# MCU.net
KiCad netlist of a schematic drawn in Altium Designer
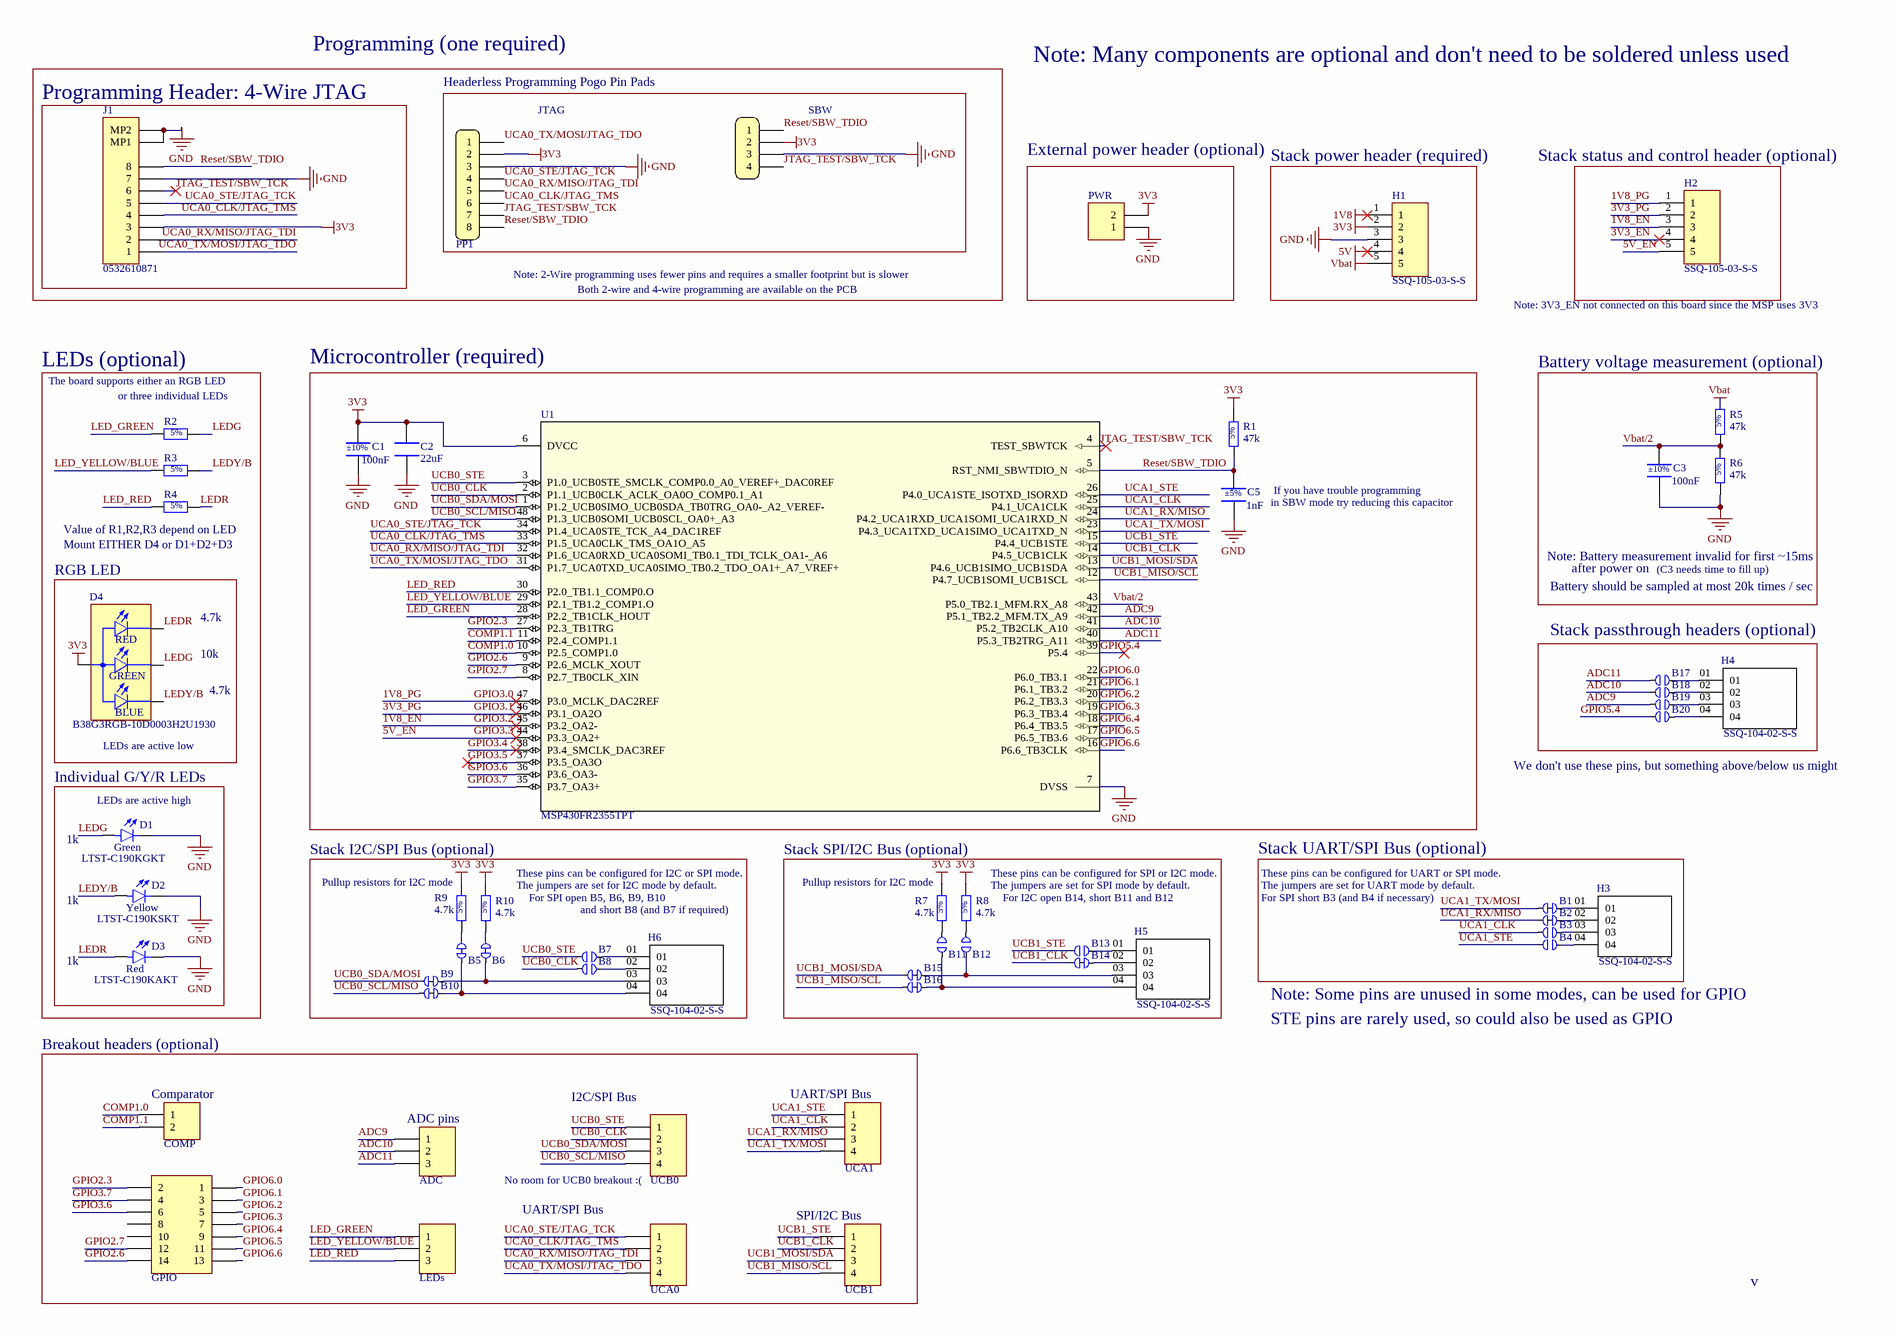
[diagram p0: MCU.SchDoc, left]
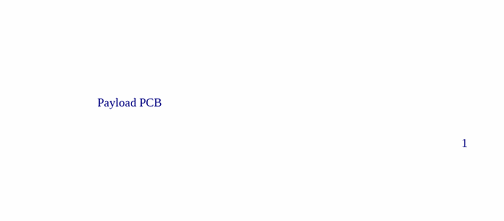
[diagram p1: MCU.SchDoc, right]

(export (version "E")
  (design (tool "Eeschema 10.0.6"))
  (components
    (comp (ref "ADC")
      (value "Header 3")
      (footprint "HDR1X3")
      (description "Header, 3-Pin")
      (libsource (lib "Miscellaneous Connectors") (part "Header 3"))
    )
    (comp (ref "B1")
      (value "Solder Jumper Normally Closed 0201")
      (footprint "Solder Bridge Closed 0201")
      (libsource (lib "APSS Generic Components") (part "Solder Jumper Normally Closed 0201"))
    )
    (comp (ref "B2")
      (value "Solder Jumper Normally Closed 0201")
      (footprint "Solder Bridge Closed 0201")
      (libsource (lib "APSS Generic Components") (part "Solder Jumper Normally Closed 0201"))
    )
    (comp (ref "B3")
      (value "Solder Jumper Normally Open 0201")
      (footprint "Solder Bridge Open 0201")
      (libsource (lib "APSS Generic Components") (part "Solder Jumper Normally Open 0201"))
    )
    (comp (ref "B4")
      (value "Solder Jumper Normally Open 0201")
      (footprint "Solder Bridge Open 0201")
      (libsource (lib "APSS Generic Components") (part "Solder Jumper Normally Open 0201"))
    )
    (comp (ref "B5")
      (value "Solder Jumper Normally Closed 0201")
      (footprint "Solder Bridge Closed 0201")
      (libsource (lib "APSS Generic Components") (part "Solder Jumper Normally Closed 0201"))
    )
    (comp (ref "B6")
      (value "Solder Jumper Normally Closed 0201")
      (footprint "Solder Bridge Closed 0201")
      (libsource (lib "APSS Generic Components") (part "Solder Jumper Normally Closed 0201"))
    )
    (comp (ref "B7")
      (value "Solder Jumper Normally Open 0201")
      (footprint "Solder Bridge Open 0201")
      (libsource (lib "") (part "Solder Jumper Normally Open 0201_1"))
    )
    (comp (ref "B8")
      (value "Solder Jumper Normally Open 0201")
      (footprint "Solder Bridge Open 0201")
      (libsource (lib "") (part "Solder Jumper Normally Open 0201_1"))
    )
    (comp (ref "B9")
      (value "Solder Jumper Normally Closed 0201")
      (footprint "Solder Bridge Closed 0201")
      (libsource (lib "APSS Generic Components") (part "Solder Jumper Normally Closed 0201"))
    )
    (comp (ref "B10")
      (value "Solder Jumper Normally Closed 0201")
      (footprint "Solder Bridge Closed 0201")
      (libsource (lib "APSS Generic Components") (part "Solder Jumper Normally Closed 0201"))
    )
    (comp (ref "B11")
      (value "Solder Jumper Normally Open 0201")
      (footprint "Solder Bridge Open 0201")
      (libsource (lib "APSS Generic Components") (part "Solder Jumper Normally Open 0201"))
    )
    (comp (ref "B12")
      (value "Solder Jumper Normally Open 0201")
      (footprint "Solder Bridge Open 0201")
      (libsource (lib "APSS Generic Components") (part "Solder Jumper Normally Open 0201"))
    )
    (comp (ref "B13")
      (value "Solder Jumper Normally Open 0201")
      (footprint "Solder Bridge Open 0201")
      (libsource (lib "APSS Generic Components") (part "Solder Jumper Normally Open 0201"))
    )
    (comp (ref "B14")
      (value "Solder Jumper Normally Closed 0201")
      (footprint "Solder Bridge Closed 0201")
      (libsource (lib "APSS Generic Components") (part "Solder Jumper Normally Closed 0201"))
    )
    (comp (ref "B15")
      (value "Solder Jumper Normally Closed 0201")
      (footprint "Solder Bridge Closed 0201")
      (libsource (lib "APSS Generic Components") (part "Solder Jumper Normally Closed 0201"))
    )
    (comp (ref "B16")
      (value "Solder Jumper Normally Closed 0201")
      (footprint "Solder Bridge Closed 0201")
      (libsource (lib "APSS Generic Components") (part "Solder Jumper Normally Closed 0201"))
    )
    (comp (ref "B17")
      (value "Solder Jumper Normally Open 0201")
      (footprint "Solder Bridge Open 0201")
      (libsource (lib "APSS Generic Components") (part "Solder Jumper Normally Open 0201"))
    )
    (comp (ref "B18")
      (value "Solder Jumper Normally Open 0201")
      (footprint "Solder Bridge Open 0201")
      (libsource (lib "APSS Generic Components") (part "Solder Jumper Normally Open 0201"))
    )
    (comp (ref "B19")
      (value "Solder Jumper Normally Open 0201")
      (footprint "Solder Bridge Open 0201")
      (libsource (lib "APSS Generic Components") (part "Solder Jumper Normally Open 0201"))
    )
    (comp (ref "B20")
      (value "Solder Jumper Normally Open 0201")
      (footprint "Solder Bridge Open 0201")
      (libsource (lib "APSS Generic Components") (part "Solder Jumper Normally Open 0201"))
    )
    (comp (ref "C1")
      (value "100nF")
      (footprint "APSS Generic Components:CAPACITOR_0805_2012M-70N")
      (description "Generic Capacitor")
      (fields (field (name "TOLERANCE") "±10%") (field (name "MF PART NO.") "C0805C104K5RAC7800"))
      (libsource (lib "General Components") (part "Generic Capacitor"))
    )
    (comp (ref "C2")
      (value "22uF")
      (footprint "APSS Prototype Parts:CAPACITOR_0805_2012M-70N")
      (description "Passive - Capacitor, X5R, 22uF Max, 6.3V, 0805 (2012 Metric), ±20%, -55°C ~ 85°C. 8.8uF @ 5V")
      (fields (field (name "TOLERANCE") "±20%") (field (name "MF PART NO.") "C0805C226M9PACTU"))
      (libsource (lib "APSS Prototype Parts") (part "C0805C226M9PACTU"))
    )
    (comp (ref "C3")
      (value "100nF")
      (footprint "APSS Generic Components:CAPACITOR_0805_2012M-70N")
      (description "Generic Capacitor")
      (fields (field (name "TOLERANCE") "±10%") (field (name "MF PART NO.") "C0805C104K5RAC7800"))
      (libsource (lib "APSS Generic Components") (part "Generic Capacitor"))
    )
    (comp (ref "C5")
      (value "1nF")
      (footprint "APSS Generic Components:CAPACITOR_0805_2012M-70N")
      (description "Generic Capacitor")
      (fields (field (name "TOLERANCE") "±5%") (field (name "MF PART NO.") "399-C0805C102J5GAC7800CT-ND"))
      (libsource (lib "APSS Generic Components") (part "Generic Capacitor"))
    )
    (comp (ref "COMP")
      (value "Header 2")
      (footprint "HDR1X2")
      (description "Header, 2-Pin")
      (libsource (lib "Miscellaneous Connectors") (part "Header 2"))
    )
    (comp (ref "D1")
      (value "LTST-C190 Series")
      (footprint "APSS Prototype Parts:LED_0603_1608M_0.80mm")
      (description "Diode - LED, 0603")
      (fields
        (field (name "MF PART NO.") "LTST-C190KGKT")
        (field (name "COLOUR") "Green")
        (field (name "APSS STANDARD PART") "APSS Standard")
      )
      (libsource (lib "APSS Prototype Parts") (part "LTST-C190 Series"))
    )
    (comp (ref "D2")
      (value "LTST-C190 Series")
      (footprint "APSS Prototype Parts:LED_0603_1608M_0.80mm")
      (description "Diode - LED, 0603")
      (fields
        (field (name "MF PART NO.") "LTST-C190KSKT")
        (field (name "COLOUR") "Yellow")
        (field (name "APSS STANDARD PART") "APSS Standard")
      )
      (libsource (lib "APSS Prototype Parts") (part "LTST-C190 Series"))
    )
    (comp (ref "D3")
      (value "LTST-C190 Series")
      (footprint "APSS Prototype Parts:LED_0603_1608M_0.80mm")
      (description "Diode - LED, 0603")
      (fields
        (field (name "MF PART NO.") "LTST-C190KAKT")
        (field (name "COLOUR") "Red")
        (field (name "APSS STANDARD PART") "APSS Standard")
      )
      (libsource (lib "APSS Prototype Parts") (part "LTST-C190 Series"))
    )
    (comp (ref "D4")
      (value "B38G3RGB-10D0003H2U1930")
      (footprint "APSS Prototype Parts:LED_B38G3RGB-10D0003H2U1930_0606_1616M")
      (description "Diode - LED, RGB, 2V Red, 3V Green, 3V Blue 0606 (1616 Metric)")
      (fields (field (name "APSS STANDARD PART") "APSS Standard"))
      (libsource (lib "APSS Prototype Parts") (part "B38G3RGB-10D0003H2U1930"))
    )
    (comp (ref "GPIO")
      (value "Header 7X2")
      (footprint "HDR2X7")
      (description "Header, 7-Pin, Dual row")
      (libsource (lib "Miscellaneous Connectors") (part "Header 7X2"))
    )
    (comp (ref "H1")
      (value "SSQ-105-03-S-S")
      (footprint "SAMTEC_SSQ-105-03-S-S:SAMTEC_SSQ-105-03-S-S")
      (libsource (lib "SSQ-105-03-S-S") (part "SSQ-105-03-S-S"))
    )
    (comp (ref "H2")
      (value "SSQ-105-03-S-S")
      (footprint "SAMTEC_SSQ-105-03-S-S:SAMTEC_SSQ-105-03-S-S")
      (libsource (lib "SSQ-105-03-S-S") (part "SSQ-105-03-S-S"))
    )
    (comp (ref "H3")
      (value "SSQ-104-02-S-S")
      (footprint "*SAMTEC_SSQ-104-02-S-S_SSQ-104-02-S-S(Primary)")
      (libsource (lib "SSQ-104-02-S-S") (part "SSQ-104-02-S-S"))
    )
    (comp (ref "H4")
      (value "SSQ-104-02-S-S")
      (footprint "*SAMTEC_SSQ-104-02-S-S_SSQ-104-02-S-S(Primary)")
      (libsource (lib "SSQ-104-02-S-S") (part "SSQ-104-02-S-S"))
    )
    (comp (ref "H5")
      (value "SSQ-104-02-S-S")
      (footprint "*SAMTEC_SSQ-104-02-S-S_SSQ-104-02-S-S(Primary)")
      (libsource (lib "SSQ-104-02-S-S") (part "SSQ-104-02-S-S"))
    )
    (comp (ref "H6")
      (value "SSQ-104-02-S-S")
      (footprint "*SAMTEC_SSQ-104-02-S-S_SSQ-104-02-S-S(Primary)")
      (libsource (lib "SSQ-104-02-S-S") (part "SSQ-104-02-S-S"))
    )
    (comp (ref "J1")
      (value "0532610871")
      (footprint "APSS Prototype Parts:MOLEX_0532610871")
      (description "Header - Picoblade 08-pin, SMT, RA")
      (fields (field (name "MF PART NO.") "0532610871") (field (name "APSS STANDARD PART") "APSS Standard"))
      (libsource (lib "APSS Prototype Parts") (part "0532610871"))
    )
    (comp (ref "LEDs")
      (value "Header 3")
      (footprint "HDR1X3")
      (description "Header, 3-Pin")
      (libsource (lib "Miscellaneous Connectors") (part "Header 3"))
    )
    (comp (ref "PP1")
      (value "Headerless Pogo Holes 8-pin")
      (footprint "POGO_8_PIN_HEADER")
      (libsource (lib "APSS Generic Components") (part "Headerless Pogo Holes 8-pin"))
    )
    (comp (ref "PP2")
      (value "Headerless Pogo Holes 4-pin")
      (footprint "APSS Generic Components:POGO_4_PIN_HEADER")
      (libsource (lib "APSS Generic Components") (part "Headerless Pogo Holes 4-pin"))
    )
    (comp (ref "PWR")
      (value "~")
      (footprint "HDR1X2")
      (description "Header, 2-Pin")
      (libsource (lib "") (part "Header 2_1"))
    )
    (comp (ref "R1")
      (value "47k")
      (footprint "APSS Flight Parts:Resistor_0805_2012M-50N")
      (fields
        (field (name "TOLERANCE") "5%")
        (field (name "POWER") "1/8W")
        (field (name "MF PART NO.") "RMCF0805JT47K0")
      )
      (libsource (lib "") (part "RMCF0805JT Series_1"))
    )
    (comp (ref "R2")
      (value "1k")
      (footprint "APSS Flight Parts:Resistor_0805_2012M-50N")
      (fields
        (field (name "TOLERANCE") "5%")
        (field (name "POWER") "1/8W")
        (field (name "MF PART NO.") "RMCF0805JT1K00")
      )
      (libsource (lib "APSS Prototype Parts") (part "RMCF0805JT Series"))
    )
    (comp (ref "R3")
      (value "1k")
      (footprint "APSS Flight Parts:Resistor_0805_2012M-50N")
      (fields
        (field (name "TOLERANCE") "5%")
        (field (name "POWER") "1/8W")
        (field (name "MF PART NO.") "RMCF0805JT1K00")
      )
      (libsource (lib "APSS Prototype Parts") (part "RMCF0805JT Series"))
    )
    (comp (ref "R4")
      (value "1k")
      (footprint "APSS Flight Parts:Resistor_0805_2012M-50N")
      (fields
        (field (name "TOLERANCE") "5%")
        (field (name "POWER") "1/8W")
        (field (name "MF PART NO.") "RMCF0805JT1K00")
      )
      (libsource (lib "APSS Prototype Parts") (part "RMCF0805JT Series"))
    )
    (comp (ref "R5")
      (value "47k")
      (footprint "APSS Flight Parts:Resistor_0805_2012M-50N")
      (fields
        (field (name "TOLERANCE") "5%")
        (field (name "POWER") "1/8W")
        (field (name "MF PART NO.") "RMCF0805JT147K0")
      )
      (libsource (lib "") (part "RMCF0805JT Series_1"))
    )
    (comp (ref "R6")
      (value "47k")
      (footprint "APSS Flight Parts:Resistor_0805_2012M-50N")
      (fields
        (field (name "TOLERANCE") "5%")
        (field (name "POWER") "1/8W")
        (field (name "MF PART NO.") "RMCF0805JT47K0")
      )
      (libsource (lib "") (part "RMCF0805JT Series_1"))
    )
    (comp (ref "R7")
      (value "4.7k")
      (footprint "APSS Flight Parts:Resistor_0805_2012M-50N")
      (fields
        (field (name "TOLERANCE") "5%")
        (field (name "POWER") "1/8W")
        (field (name "MF PART NO.") "RMCF0805JT4K70")
      )
      (libsource (lib "") (part "RMCF0805JT Series_1"))
    )
    (comp (ref "R8")
      (value "4.7k")
      (footprint "APSS Flight Parts:Resistor_0805_2012M-50N")
      (fields
        (field (name "TOLERANCE") "5%")
        (field (name "POWER") "1/8W")
        (field (name "MF PART NO.") "RMCF0805JT4K70")
      )
      (libsource (lib "") (part "RMCF0805JT Series_1"))
    )
    (comp (ref "R9")
      (value "4.7k")
      (footprint "APSS Flight Parts:Resistor_0805_2012M-50N")
      (fields
        (field (name "TOLERANCE") "5%")
        (field (name "POWER") "1/8W")
        (field (name "MF PART NO.") "RMCF0805JT4K70")
      )
      (libsource (lib "") (part "RMCF0805JT Series_1"))
    )
    (comp (ref "R10")
      (value "4.7k")
      (footprint "APSS Flight Parts:Resistor_0805_2012M-50N")
      (fields
        (field (name "TOLERANCE") "5%")
        (field (name "POWER") "1/8W")
        (field (name "MF PART NO.") "RMCF0805JT4K70")
      )
      (libsource (lib "") (part "RMCF0805JT Series_1"))
    )
    (comp (ref "U1")
      (value "MSP430FR2355TPT")
      (footprint "PT0048A_L")
      (fields (field (name "APSS STANDARD PART") "APSS Standard"))
      (libsource (lib "MSP430") (part "MSP430FR2355IPT"))
    )
    (comp (ref "UCA0")
      (value "Header 4")
      (footprint "HDR1X4")
      (description "Header, 4-Pin")
      (libsource (lib "Miscellaneous Connectors") (part "Header 4"))
    )
    (comp (ref "UCA1")
      (value "Header 4")
      (footprint "HDR1X4")
      (description "Header, 4-Pin")
      (libsource (lib "Miscellaneous Connectors") (part "Header 4"))
    )
    (comp (ref "UCB0")
      (value "Header 4")
      (footprint "HDR1X4")
      (description "Header, 4-Pin")
      (libsource (lib "Miscellaneous Connectors") (part "Header 4"))
    )
    (comp (ref "UCB1")
      (value "Header 4")
      (footprint "HDR1X4")
      (description "Header, 4-Pin")
      (libsource (lib "Miscellaneous Connectors") (part "Header 4"))
    )
  )
  (nets
    (net (code "1") (name "/1V8_EN") (class "Default")
      (node (ref "H2") (pin "3") (pinfunction "3_3") (pintype "passive"))
      (node (ref "U1") (pin "45") (pinfunction "P3.2_OA2-_45") (pintype "bidirectional"))
    )
    (net (code "2") (name "/1V8_PG") (class "Default")
      (node (ref "H2") (pin "1") (pinfunction "1_1") (pintype "passive"))
      (node (ref "U1") (pin "47") (pinfunction "P3.0_MCLK_DAC2REF_47") (pintype "bidirectional"))
    )
    (net (code "3") (name "/3V3_EN") (class "Default")
      (node (ref "H2") (pin "4") (pinfunction "4_4") (pintype "passive+no_connect"))
    )
    (net (code "4") (name "/3V3_PG") (class "Default")
      (node (ref "H2") (pin "2") (pinfunction "2_2") (pintype "passive"))
      (node (ref "U1") (pin "46") (pinfunction "P3.1_OA2O_46") (pintype "bidirectional"))
    )
    (net (code "5") (name "/5V_EN") (class "Default")
      (node (ref "H2") (pin "5") (pinfunction "5_5") (pintype "passive"))
      (node (ref "U1") (pin "44") (pinfunction "P3.3_OA2+_44") (pintype "bidirectional"))
    )
    (net (code "7") (name "/ADC9") (class "Default")
      (node (ref "ADC") (pin "1") (pinfunction "1_1") (pintype "passive"))
      (node (ref "B19") (pin "1") (pinfunction "1_1") (pintype "passive"))
      (node (ref "U1") (pin "42") (pinfunction "P5.1_TB2.2_MFM.TX_A9_42") (pintype "bidirectional"))
    )
    (net (code "8") (name "/ADC10") (class "Default")
      (node (ref "ADC") (pin "2") (pinfunction "2_2") (pintype "passive"))
      (node (ref "B18") (pin "1") (pinfunction "1_1") (pintype "passive"))
      (node (ref "U1") (pin "41") (pinfunction "P5.2_TB2CLK_A10_41") (pintype "bidirectional"))
    )
    (net (code "9") (name "/ADC11") (class "Default")
      (node (ref "ADC") (pin "3") (pinfunction "3_3") (pintype "passive"))
      (node (ref "B17") (pin "1") (pinfunction "1_1") (pintype "passive"))
      (node (ref "U1") (pin "40") (pinfunction "P5.3_TB2TRG_A11_40") (pintype "bidirectional"))
    )
    (net (code "10") (name "/COMP1.0") (class "Default")
      (node (ref "COMP") (pin "1") (pinfunction "1_1") (pintype "passive"))
      (node (ref "U1") (pin "10") (pinfunction "P2.5_COMP1.0_10") (pintype "bidirectional"))
    )
    (net (code "11") (name "/COMP1.1") (class "Default")
      (node (ref "COMP") (pin "2") (pinfunction "2_2") (pintype "passive"))
      (node (ref "U1") (pin "11") (pinfunction "P2.4_COMP1.1_11") (pintype "bidirectional"))
    )
    (net (code "12") (name "/GPIO2.3") (class "Default")
      (node (ref "GPIO") (pin "2") (pinfunction "2_2") (pintype "passive"))
      (node (ref "U1") (pin "27") (pinfunction "P2.3_TB1TRG_27") (pintype "bidirectional"))
    )
    (net (code "13") (name "/GPIO2.6") (class "Default")
      (node (ref "GPIO") (pin "14") (pinfunction "14_14") (pintype "passive"))
      (node (ref "U1") (pin "9") (pinfunction "P2.6_MCLK_XOUT_9") (pintype "bidirectional"))
    )
    (net (code "14") (name "/GPIO2.7") (class "Default")
      (node (ref "GPIO") (pin "12") (pinfunction "12_12") (pintype "passive"))
      (node (ref "U1") (pin "8") (pinfunction "P2.7_TB0CLK_XIN_8") (pintype "bidirectional"))
    )
    (net (code "15") (name "/GPIO3.4") (class "Default")
      (node (ref "U1") (pin "38") (pinfunction "P3.4_SMCLK_DAC3REF_38") (pintype "bidirectional+no_connect"))
    )
    (net (code "16") (name "/GPIO3.5") (class "Default")
      (node (ref "U1") (pin "37") (pinfunction "P3.5_OA3O_37") (pintype "bidirectional+no_connect"))
    )
    (net (code "17") (name "/GPIO3.6") (class "Default")
      (node (ref "GPIO") (pin "6") (pinfunction "6_6") (pintype "passive"))
      (node (ref "U1") (pin "36") (pinfunction "P3.6_OA3-_36") (pintype "bidirectional"))
    )
    (net (code "18") (name "/GPIO3.7") (class "Default")
      (node (ref "GPIO") (pin "4") (pinfunction "4_4") (pintype "passive"))
      (node (ref "U1") (pin "35") (pinfunction "P3.7_OA3+_35") (pintype "bidirectional"))
    )
    (net (code "19") (name "/GPIO5.4") (class "Default")
      (node (ref "B20") (pin "1") (pinfunction "1_1") (pintype "passive"))
      (node (ref "U1") (pin "39") (pinfunction "P5.4_39") (pintype "bidirectional"))
    )
    (net (code "20") (name "/GPIO6.0") (class "Default")
      (node (ref "GPIO") (pin "1") (pinfunction "1_1") (pintype "passive"))
      (node (ref "U1") (pin "22") (pinfunction "P6.0_TB3.1_22") (pintype "bidirectional"))
    )
    (net (code "21") (name "/GPIO6.1") (class "Default")
      (node (ref "GPIO") (pin "3") (pinfunction "3_3") (pintype "passive"))
      (node (ref "U1") (pin "21") (pinfunction "P6.1_TB3.2_21") (pintype "bidirectional"))
    )
    (net (code "22") (name "/GPIO6.2") (class "Default")
      (node (ref "GPIO") (pin "5") (pinfunction "5_5") (pintype "passive"))
      (node (ref "U1") (pin "20") (pinfunction "P6.2_TB3.3_20") (pintype "bidirectional"))
    )
    (net (code "23") (name "/GPIO6.3") (class "Default")
      (node (ref "GPIO") (pin "7") (pinfunction "7_7") (pintype "passive"))
      (node (ref "U1") (pin "19") (pinfunction "P6.3_TB3.4_19") (pintype "bidirectional"))
    )
    (net (code "24") (name "/GPIO6.4") (class "Default")
      (node (ref "GPIO") (pin "9") (pinfunction "9_9") (pintype "passive"))
      (node (ref "U1") (pin "18") (pinfunction "P6.4_TB3.5_18") (pintype "bidirectional"))
    )
    (net (code "25") (name "/GPIO6.5") (class "Default")
      (node (ref "GPIO") (pin "11") (pinfunction "11_11") (pintype "passive"))
      (node (ref "U1") (pin "17") (pinfunction "P6.5_TB3.6_17") (pintype "bidirectional"))
    )
    (net (code "26") (name "/GPIO6.6") (class "Default")
      (node (ref "GPIO") (pin "13") (pinfunction "13_13") (pintype "passive"))
      (node (ref "U1") (pin "16") (pinfunction "P6.6_TB3CLK_16") (pintype "bidirectional"))
    )
    (net (code "27") (name "/JTAG_TEST{slash}SBW_TCK") (class "Default")
      (node (ref "J1") (pin "6") (pinfunction "6_6") (pintype "passive"))
      (node (ref "PP1") (pin "7") (pinfunction "7_7") (pintype "passive"))
      (node (ref "PP2") (pin "4") (pinfunction "4_4") (pintype "passive"))
      (node (ref "U1") (pin "4") (pinfunction "TEST_SBWTCK_4") (pintype "input"))
    )
    (net (code "28") (name "/LEDG") (class "Default")
      (node (ref "D1") (pin "A") (pinfunction "A_A") (pintype "passive"))
      (node (ref "D4") (pin "1") (pinfunction "G_C_1") (pintype "passive"))
      (node (ref "R2") (pin "2") (pinfunction "2_2") (pintype "passive"))
    )
    (net (code "29") (name "/LEDR") (class "Default")
      (node (ref "D3") (pin "A") (pinfunction "A_A") (pintype "passive"))
      (node (ref "D4") (pin "4") (pinfunction "R_C_4") (pintype "passive"))
      (node (ref "R4") (pin "2") (pinfunction "2_2") (pintype "passive"))
    )
    (net (code "30") (name "/LEDY{slash}B") (class "Default")
      (node (ref "D2") (pin "A") (pinfunction "A_A") (pintype "passive"))
      (node (ref "D4") (pin "2") (pinfunction "B_C_2") (pintype "passive"))
      (node (ref "R3") (pin "2") (pinfunction "2_2") (pintype "passive"))
    )
    (net (code "31") (name "/LED_GREEN") (class "Default")
      (node (ref "LEDs") (pin "1") (pinfunction "1_1") (pintype "passive"))
      (node (ref "R2") (pin "1") (pinfunction "1_1") (pintype "passive"))
      (node (ref "U1") (pin "28") (pinfunction "P2.2_TB1CLK_HOUT_28") (pintype "bidirectional"))
    )
    (net (code "32") (name "/LED_RED") (class "Default")
      (node (ref "LEDs") (pin "3") (pinfunction "3_3") (pintype "passive"))
      (node (ref "R4") (pin "1") (pinfunction "1_1") (pintype "passive"))
      (node (ref "U1") (pin "30") (pinfunction "P2.0_TB1.1_COMP0.O_30") (pintype "bidirectional"))
    )
    (net (code "33") (name "/LED_YELLOW{slash}BLUE") (class "Default")
      (node (ref "LEDs") (pin "2") (pinfunction "2_2") (pintype "passive"))
      (node (ref "R3") (pin "1") (pinfunction "1_1") (pintype "passive"))
      (node (ref "U1") (pin "29") (pinfunction "P2.1_TB1.2_COMP1.O_29") (pintype "bidirectional"))
    )
    (net (code "34") (name "/Reset{slash}SBW_TDIO") (class "Default")
      (node (ref "C5") (pin "2") (pinfunction "2_2") (pintype "passive"))
      (node (ref "J1") (pin "8") (pinfunction "8_8") (pintype "passive"))
      (node (ref "PP1") (pin "8") (pinfunction "8_8") (pintype "passive"))
      (node (ref "PP2") (pin "1") (pinfunction "1_1") (pintype "passive"))
      (node (ref "R1") (pin "1") (pinfunction "1_1") (pintype "passive"))
      (node (ref "U1") (pin "5") (pinfunction "RST_NMI_SBWTDIO_N_5") (pintype "bidirectional"))
    )
    (net (code "35") (name "/UCA0_CLK{slash}JTAG_TMS") (class "Default")
      (node (ref "J1") (pin "4") (pinfunction "4_4") (pintype "passive"))
      (node (ref "PP1") (pin "6") (pinfunction "6_6") (pintype "passive"))
      (node (ref "U1") (pin "33") (pinfunction "P1.5_UCA0CLK_TMS_OA1O_A5_33") (pintype "bidirectional"))
      (node (ref "UCA0") (pin "2") (pinfunction "2_2") (pintype "passive"))
    )
    (net (code "36") (name "/UCA0_RX{slash}MISO{slash}JTAG_TDI") (class "Default")
      (node (ref "J1") (pin "2") (pinfunction "2_2") (pintype "passive"))
      (node (ref "PP1") (pin "5") (pinfunction "5_5") (pintype "passive"))
      (node (ref "U1") (pin "32") (pinfunction "P1.6_UCA0RXD_UCA0SOMI_TB0.1_TDI_TCLK_OA1-_A6_32") (pintype "bidirectional"))
      (node (ref "UCA0") (pin "3") (pinfunction "3_3") (pintype "passive"))
    )
    (net (code "37") (name "/UCA0_STE{slash}JTAG_TCK") (class "Default")
      (node (ref "J1") (pin "5") (pinfunction "5_5") (pintype "passive"))
      (node (ref "PP1") (pin "4") (pinfunction "4_4") (pintype "passive"))
      (node (ref "U1") (pin "34") (pinfunction "P1.4_UCA0STE_TCK_A4_DAC1REF_34") (pintype "bidirectional"))
      (node (ref "UCA0") (pin "1") (pinfunction "1_1") (pintype "passive"))
    )
    (net (code "38") (name "/UCA0_TX{slash}MOSI{slash}JTAG_TDO") (class "Default")
      (node (ref "J1") (pin "1") (pinfunction "1_1") (pintype "passive"))
      (node (ref "PP1") (pin "1") (pinfunction "1_1") (pintype "passive"))
      (node (ref "U1") (pin "31") (pinfunction "P1.7_UCA0TXD_UCA0SIMO_TB0.2_TDO_OA1+_A7_VREF+_31") (pintype "bidirectional"))
      (node (ref "UCA0") (pin "4") (pinfunction "4_4") (pintype "passive"))
    )
    (net (code "39") (name "/UCA1_CLK") (class "Default")
      (node (ref "B3") (pin "1") (pinfunction "1_1") (pintype "passive"))
      (node (ref "U1") (pin "25") (pinfunction "P4.1_UCA1CLK_25") (pintype "bidirectional"))
      (node (ref "UCA1") (pin "2") (pinfunction "2_2") (pintype "passive"))
    )
    (net (code "40") (name "/UCA1_RX{slash}MISO") (class "Default")
      (node (ref "B2") (pin "1") (pinfunction "1_1") (pintype "passive"))
      (node (ref "U1") (pin "24") (pinfunction "P4.2_UCA1RXD_UCA1SOMI_UCA1RXD_N_24") (pintype "bidirectional"))
      (node (ref "UCA1") (pin "3") (pinfunction "3_3") (pintype "passive"))
    )
    (net (code "41") (name "/UCA1_STE") (class "Default")
      (node (ref "B4") (pin "1") (pinfunction "1_1") (pintype "passive"))
      (node (ref "U1") (pin "26") (pinfunction "P4.0_UCA1STE_ISOTXD_ISORXD_26") (pintype "bidirectional"))
      (node (ref "UCA1") (pin "1") (pinfunction "1_1") (pintype "passive"))
    )
    (net (code "42") (name "/UCA1_TX{slash}MOSI") (class "Default")
      (node (ref "B1") (pin "1") (pinfunction "1_1") (pintype "passive"))
      (node (ref "U1") (pin "23") (pinfunction "P4.3_UCA1TXD_UCA1SIMO_UCA1TXD_N_23") (pintype "bidirectional"))
      (node (ref "UCA1") (pin "4") (pinfunction "4_4") (pintype "passive"))
    )
    (net (code "43") (name "/UCB0_CLK") (class "Default")
      (node (ref "B8") (pin "2") (pinfunction "2_2") (pintype "passive"))
      (node (ref "U1") (pin "2") (pinfunction "P1.1_UCB0CLK_ACLK_OA0O_COMP0.1_A1_2") (pintype "bidirectional"))
      (node (ref "UCB0") (pin "2") (pinfunction "2_2") (pintype "passive"))
    )
    (net (code "44") (name "/UCB0_SCL{slash}MISO") (class "Default")
      (node (ref "B10") (pin "1") (pinfunction "1_1") (pintype "passive"))
      (node (ref "U1") (pin "48") (pinfunction "P1.3_UCB0SOMI_UCB0SCL_OA0+_A3_48") (pintype "bidirectional"))
      (node (ref "UCB0") (pin "4") (pinfunction "4_4") (pintype "passive"))
    )
    (net (code "45") (name "/UCB0_SDA{slash}MOSI") (class "Default")
      (node (ref "B9") (pin "2") (pinfunction "2_2") (pintype "passive"))
      (node (ref "U1") (pin "1") (pinfunction "P1.2_UCB0SIMO_UCB0SDA_TB0TRG_OA0-_A2_VEREF-_1") (pintype "bidirectional"))
      (node (ref "UCB0") (pin "3") (pinfunction "3_3") (pintype "passive"))
    )
    (net (code "46") (name "/UCB0_STE") (class "Default")
      (node (ref "B7") (pin "2") (pinfunction "2_2") (pintype "passive"))
      (node (ref "U1") (pin "3") (pinfunction "P1.0_UCB0STE_SMCLK_COMP0.0_A0_VEREF+_DAC0REF_3") (pintype "bidirectional"))
      (node (ref "UCB0") (pin "1") (pinfunction "1_1") (pintype "passive"))
    )
    (net (code "47") (name "/UCB1_CLK") (class "Default")
      (node (ref "B14") (pin "1") (pinfunction "1_1") (pintype "passive"))
      (node (ref "U1") (pin "14") (pinfunction "P4.5_UCB1CLK_14") (pintype "bidirectional"))
      (node (ref "UCB1") (pin "2") (pinfunction "2_2") (pintype "passive"))
    )
    (net (code "48") (name "/UCB1_MISO{slash}SCL") (class "Default")
      (node (ref "B16") (pin "1") (pinfunction "1_1") (pintype "passive"))
      (node (ref "U1") (pin "12") (pinfunction "P4.7_UCB1SOMI_UCB1SCL_12") (pintype "bidirectional"))
      (node (ref "UCB1") (pin "4") (pinfunction "4_4") (pintype "passive"))
    )
    (net (code "49") (name "/UCB1_MOSI{slash}SDA") (class "Default")
      (node (ref "B15") (pin "1") (pinfunction "1_1") (pintype "passive"))
      (node (ref "U1") (pin "13") (pinfunction "P4.6_UCB1SIMO_UCB1SDA_13") (pintype "bidirectional"))
      (node (ref "UCB1") (pin "3") (pinfunction "3_3") (pintype "passive"))
    )
    (net (code "50") (name "/UCB1_STE") (class "Default")
      (node (ref "B13") (pin "1") (pinfunction "1_1") (pintype "passive"))
      (node (ref "U1") (pin "15") (pinfunction "P4.4_UCB1STE_15") (pintype "bidirectional"))
      (node (ref "UCB1") (pin "1") (pinfunction "1_1") (pintype "passive"))
    )
    (net (code "51") (name "/Vbat{slash}2") (class "Default")
      (node (ref "C3") (pin "2") (pinfunction "2_2") (pintype "passive"))
      (node (ref "R5") (pin "1") (pinfunction "1_1") (pintype "passive"))
      (node (ref "R6") (pin "2") (pinfunction "2_2") (pintype "passive"))
      (node (ref "U1") (pin "43") (pinfunction "P5.0_TB2.1_MFM.RX_A8_43") (pintype "bidirectional"))
    )
    (net (code "52") (name "1V8") (class "Default")
      (node (ref "H1") (pin "1") (pinfunction "1_1") (pintype "passive"))
    )
    (net (code "53") (name "3V3") (class "Default")
      (node (ref "C1") (pin "2") (pinfunction "2_2") (pintype "passive"))
      (node (ref "C2") (pin "2") (pinfunction "2_2") (pintype "passive"))
      (node (ref "D4") (pin "3") (pinfunction "A_3") (pintype "passive"))
      (node (ref "H1") (pin "2") (pinfunction "2_2") (pintype "passive"))
      (node (ref "J1") (pin "3") (pinfunction "3_3") (pintype "passive"))
      (node (ref "PP1") (pin "2") (pinfunction "2_2") (pintype "passive"))
      (node (ref "PP2") (pin "2") (pinfunction "2_2") (pintype "passive"))
      (node (ref "PWR") (pin "2") (pinfunction "2_2") (pintype "passive"))
      (node (ref "R1") (pin "2") (pinfunction "2_2") (pintype "passive"))
      (node (ref "R10") (pin "2") (pinfunction "2_2") (pintype "passive"))
      (node (ref "R7") (pin "2") (pinfunction "2_2") (pintype "passive"))
      (node (ref "R8") (pin "2") (pinfunction "2_2") (pintype "passive"))
      (node (ref "R9") (pin "2") (pinfunction "2_2") (pintype "passive"))
      (node (ref "U1") (pin "6") (pinfunction "DVCC_6") (pintype "power_in"))
    )
    (net (code "54") (name "5V") (class "Default")
      (node (ref "H1") (pin "4") (pinfunction "4_4") (pintype "passive"))
    )
    (net (code "55") (name "GND") (class "Default")
      (node (ref "C1") (pin "1") (pinfunction "1_1") (pintype "passive"))
      (node (ref "C2") (pin "1") (pinfunction "1_1") (pintype "passive"))
      (node (ref "C3") (pin "1") (pinfunction "1_1") (pintype "passive"))
      (node (ref "C5") (pin "1") (pinfunction "1_1") (pintype "passive"))
      (node (ref "D1") (pin "C") (pinfunction "C_C") (pintype "passive"))
      (node (ref "D2") (pin "C") (pinfunction "C_C") (pintype "passive"))
      (node (ref "D3") (pin "C") (pinfunction "C_C") (pintype "passive"))
      (node (ref "H1") (pin "3") (pinfunction "3_3") (pintype "passive"))
      (node (ref "J1") (pin "7") (pinfunction "7_7") (pintype "passive"))
      (node (ref "J1") (pin "MP1") (pinfunction "MP1_MP1") (pintype "passive"))
      (node (ref "J1") (pin "MP2") (pinfunction "MP2_MP2") (pintype "passive"))
      (node (ref "PP1") (pin "3") (pinfunction "3_3") (pintype "passive"))
      (node (ref "PP2") (pin "3") (pinfunction "3_3") (pintype "passive"))
      (node (ref "PWR") (pin "1") (pinfunction "1_1") (pintype "passive"))
      (node (ref "R6") (pin "1") (pinfunction "1_1") (pintype "passive"))
      (node (ref "U1") (pin "7") (pinfunction "DVSS_7") (pintype "power_in"))
    )
    (net (code "56") (name "Net-(B1-Pad2)") (class "Default")
      (node (ref "B1") (pin "2") (pinfunction "2_2") (pintype "passive"))
      (node (ref "H3") (pin "01") (pinfunction "01_01") (pintype "passive"))
    )
    (net (code "57") (name "Net-(B2-Pad2)") (class "Default")
      (node (ref "B2") (pin "2") (pinfunction "2_2") (pintype "passive"))
      (node (ref "H3") (pin "02") (pinfunction "02_02") (pintype "passive"))
    )
    (net (code "58") (name "Net-(B3-Pad2)") (class "Default")
      (node (ref "B3") (pin "2") (pinfunction "2_2") (pintype "passive"))
      (node (ref "H3") (pin "03") (pinfunction "03_03") (pintype "passive"))
    )
    (net (code "59") (name "Net-(B4-Pad2)") (class "Default")
      (node (ref "B4") (pin "2") (pinfunction "2_2") (pintype "passive"))
      (node (ref "H3") (pin "04") (pinfunction "04_04") (pintype "passive"))
    )
    (net (code "60") (name "Net-(B5-Pad2)") (class "Default")
      (node (ref "B5") (pin "2") (pinfunction "2_2") (pintype "passive"))
      (node (ref "R9") (pin "1") (pinfunction "1_1") (pintype "passive"))
    )
    (net (code "61") (name "Net-(B6-Pad1)") (class "Default")
      (node (ref "B6") (pin "1") (pinfunction "1_1") (pintype "passive"))
      (node (ref "R10") (pin "1") (pinfunction "1_1") (pintype "passive"))
    )
    (net (code "62") (name "Net-(B6-Pad2)") (class "Default")
      (node (ref "B6") (pin "2") (pinfunction "2_2") (pintype "passive"))
      (node (ref "B9") (pin "1") (pinfunction "1_1") (pintype "passive"))
      (node (ref "H6") (pin "03") (pinfunction "03_03") (pintype "passive"))
    )
    (net (code "63") (name "Net-(B7-Pad1)") (class "Default")
      (node (ref "B7") (pin "1") (pinfunction "1_1") (pintype "passive"))
      (node (ref "H6") (pin "01") (pinfunction "01_01") (pintype "passive"))
    )
    (net (code "64") (name "Net-(B8-Pad1)") (class "Default")
      (node (ref "B8") (pin "1") (pinfunction "1_1") (pintype "passive"))
      (node (ref "H6") (pin "02") (pinfunction "02_02") (pintype "passive"))
    )
    (net (code "65") (name "Net-(B10-Pad2)") (class "Default")
      (node (ref "B10") (pin "2") (pinfunction "2_2") (pintype "passive"))
      (node (ref "B5") (pin "1") (pinfunction "1_1") (pintype "passive"))
      (node (ref "H6") (pin "04") (pinfunction "04_04") (pintype "passive"))
    )
    (net (code "66") (name "Net-(B11-Pad1)") (class "Default")
      (node (ref "B11") (pin "1") (pinfunction "1_1") (pintype "passive"))
      (node (ref "B16") (pin "2") (pinfunction "2_2") (pintype "passive"))
      (node (ref "H5") (pin "04") (pinfunction "04_04") (pintype "passive"))
    )
    (net (code "67") (name "Net-(B11-Pad2)") (class "Default")
      (node (ref "B11") (pin "2") (pinfunction "2_2") (pintype "passive"))
      (node (ref "R7") (pin "1") (pinfunction "1_1") (pintype "passive"))
    )
    (net (code "68") (name "Net-(B12-Pad1)") (class "Default")
      (node (ref "B12") (pin "1") (pinfunction "1_1") (pintype "passive"))
      (node (ref "R8") (pin "1") (pinfunction "1_1") (pintype "passive"))
    )
    (net (code "69") (name "Net-(B12-Pad2)") (class "Default")
      (node (ref "B12") (pin "2") (pinfunction "2_2") (pintype "passive"))
      (node (ref "B15") (pin "2") (pinfunction "2_2") (pintype "passive"))
      (node (ref "H5") (pin "03") (pinfunction "03_03") (pintype "passive"))
    )
    (net (code "70") (name "Net-(B13-Pad2)") (class "Default")
      (node (ref "B13") (pin "2") (pinfunction "2_2") (pintype "passive"))
      (node (ref "H5") (pin "01") (pinfunction "01_01") (pintype "passive"))
    )
    (net (code "71") (name "Net-(B14-Pad2)") (class "Default")
      (node (ref "B14") (pin "2") (pinfunction "2_2") (pintype "passive"))
      (node (ref "H5") (pin "02") (pinfunction "02_02") (pintype "passive"))
    )
    (net (code "72") (name "Net-(B17-Pad2)") (class "Default")
      (node (ref "B17") (pin "2") (pinfunction "2_2") (pintype "passive"))
      (node (ref "H4") (pin "01") (pinfunction "01_01") (pintype "passive"))
    )
    (net (code "73") (name "Net-(B18-Pad2)") (class "Default")
      (node (ref "B18") (pin "2") (pinfunction "2_2") (pintype "passive"))
      (node (ref "H4") (pin "02") (pinfunction "02_02") (pintype "passive"))
    )
    (net (code "74") (name "Net-(B19-Pad2)") (class "Default")
      (node (ref "B19") (pin "2") (pinfunction "2_2") (pintype "passive"))
      (node (ref "H4") (pin "03") (pinfunction "03_03") (pintype "passive"))
    )
    (net (code "75") (name "Net-(B20-Pad2)") (class "Default")
      (node (ref "B20") (pin "2") (pinfunction "2_2") (pintype "passive"))
      (node (ref "H4") (pin "04") (pinfunction "04_04") (pintype "passive"))
    )
    (net (code "76") (name "Vbat") (class "Default")
      (node (ref "H1") (pin "5") (pinfunction "5_5") (pintype "passive"))
      (node (ref "R5") (pin "2") (pinfunction "2_2") (pintype "passive"))
    )
    (net (code "77") (name "unconnected-(GPIO-Pad8)") (class "Default")
      (node (ref "GPIO") (pin "8") (pinfunction "8_8") (pintype "passive"))
    )
    (net (code "78") (name "unconnected-(GPIO-Pad10)") (class "Default")
      (node (ref "GPIO") (pin "10") (pinfunction "10_10") (pintype "passive"))
    )
  )
)
